# radio_board.net
KiCad netlist of a schematic drawn in EAGLE
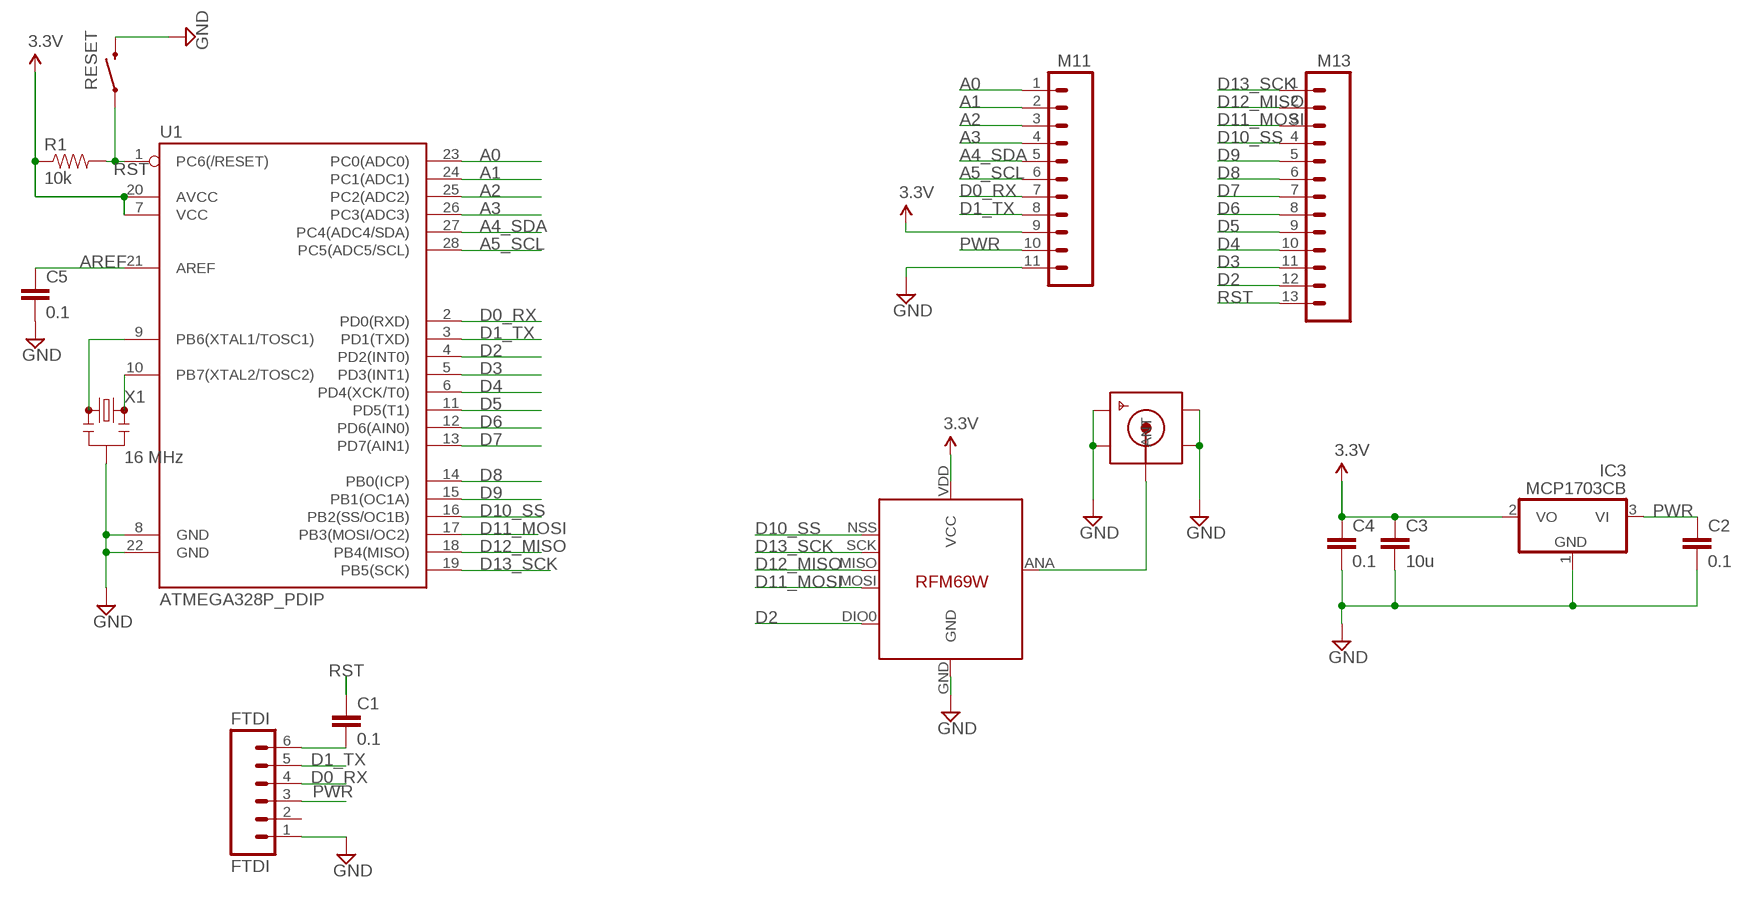
[diagram p0: schematic, sheet 1]

(export (version "E")
  (design (tool "Eeschema 10.0.6"))
  (components
    (comp (ref "C1")
      (value "0.1")
      (footprint "eagle-import:CAP-PTH-SMALL")
      (libsource (lib "eagle-import") (part "CAPPTH"))
    )
    (comp (ref "C2")
      (value "0.1")
      (footprint "eagle-import:CAP-PTH-SMALL")
      (libsource (lib "eagle-import") (part "CAPPTH"))
    )
    (comp (ref "C3")
      (value "10u")
      (footprint "eagle-import:CAP-PTH-SMALL")
      (libsource (lib "eagle-import") (part "CAPPTH"))
    )
    (comp (ref "C4")
      (value "0.1")
      (footprint "eagle-import:CAP-PTH-SMALL")
      (libsource (lib "eagle-import") (part "CAPPTH"))
    )
    (comp (ref "C5")
      (value "0.1")
      (footprint "eagle-import:CAP-PTH-SMALL")
      (libsource (lib "eagle-import") (part "CAPPTH"))
    )
    (comp (ref "DIGITALSIDE")
      (value "M13")
      (footprint "eagle-import:1X13")
      (libsource (lib "eagle-import") (part "M13"))
    )
    (comp (ref "FTDI")
      (value "FTDI")
      (footprint "eagle-import:1X06")
      (libsource (lib "eagle-import") (part "M06SIP"))
    )
    (comp (ref "IC3")
      (value "MCP1703CB")
      (footprint "eagle-import:SOT23")
      (libsource (lib "eagle-import") (part "MCP1703CB"))
    )
    (comp (ref "M11")
      (value "M11PTH")
      (footprint "eagle-import:1X11")
      (libsource (lib "eagle-import") (part "M11PTH"))
    )
    (comp (ref "R1")
      (value "10k")
      (footprint "eagle-import:AXIAL-0.4")
      (libsource (lib "eagle-import") (part "RESISTORPTH-1/4W"))
    )
    (comp (ref "RESET")
      (value "SWITCH-MOMENTARY-2SMD")
      (footprint "eagle-import:TACTILE-SWITCH-SMD")
      (libsource (lib "eagle-import") (part "SWITCH-MOMENTARY-2SMD"))
    )
    (comp (ref "SMA_CONNECTOR")
      (value "SMACONNECTOR_EDGE")
      (footprint "eagle-import:SMA_EDGELAUNCH")
      (libsource (lib "eagle-import") (part "SMACONNECTOR_EDGE"))
    )
    (comp (ref "U$5")
      (value "RFM69HW")
      (footprint "eagle-import:RFM69W-MINPADS")
      (libsource (lib "eagle-import") (part "RFM69"))
    )
    (comp (ref "U1")
      (value "ATMEGA328P_PDIP")
      (footprint "eagle-import:DIL28-3")
      (libsource (lib "eagle-import") (part "ATMEGA328P_PDIP"))
    )
    (comp (ref "X1")
      (value "16 MHz")
      (footprint "eagle-import:RESONATOR-PTH")
      (libsource (lib "eagle-import") (part "RESONATORPTH"))
    )
  )
  (nets
    (net (code "1") (name "/A0") (class "Default")
      (node (ref "M11") (pin "1") (pinfunction "1_1") (pintype "passive"))
      (node (ref "U1") (pin "23") (pinfunction "PC0(ADC0)_23") (pintype "bidirectional"))
    )
    (net (code "2") (name "/A1") (class "Default")
      (node (ref "M11") (pin "2") (pinfunction "2_2") (pintype "passive"))
      (node (ref "U1") (pin "24") (pinfunction "PC1(ADC1)_24") (pintype "bidirectional"))
    )
    (net (code "3") (name "/A2") (class "Default")
      (node (ref "M11") (pin "3") (pinfunction "3_3") (pintype "passive"))
      (node (ref "U1") (pin "25") (pinfunction "PC2(ADC2)_25") (pintype "bidirectional"))
    )
    (net (code "4") (name "/A3") (class "Default")
      (node (ref "M11") (pin "4") (pinfunction "4_4") (pintype "passive"))
      (node (ref "U1") (pin "26") (pinfunction "PC3(ADC3)_26") (pintype "bidirectional"))
    )
    (net (code "5") (name "/A4_SDA") (class "Default")
      (node (ref "M11") (pin "5") (pinfunction "5_5") (pintype "passive"))
      (node (ref "U1") (pin "27") (pinfunction "PC4(ADC4/SDA)_27") (pintype "bidirectional"))
    )
    (net (code "6") (name "/A5_SCL") (class "Default")
      (node (ref "M11") (pin "6") (pinfunction "6_6") (pintype "passive"))
      (node (ref "U1") (pin "28") (pinfunction "PC5(ADC5/SCL)_28") (pintype "bidirectional"))
    )
    (net (code "7") (name "/AREF") (class "Default")
      (node (ref "C5") (pin "1") (pinfunction "1_1") (pintype "passive"))
      (node (ref "U1") (pin "21") (pinfunction "AREF_21") (pintype "bidirectional"))
    )
    (net (code "8") (name "/D0_RX") (class "Default")
      (node (ref "FTDI") (pin "4") (pinfunction "4_4") (pintype "passive"))
      (node (ref "M11") (pin "7") (pinfunction "7_7") (pintype "passive"))
      (node (ref "U1") (pin "2") (pinfunction "PD0(RXD)_2") (pintype "bidirectional"))
    )
    (net (code "9") (name "/D1_TX") (class "Default")
      (node (ref "FTDI") (pin "5") (pinfunction "5_5") (pintype "passive"))
      (node (ref "M11") (pin "8") (pinfunction "8_8") (pintype "passive"))
      (node (ref "U1") (pin "3") (pinfunction "PD1(TXD)_3") (pintype "bidirectional"))
    )
    (net (code "10") (name "/D2") (class "Default")
      (node (ref "DIGITALSIDE") (pin "12") (pinfunction "12_12") (pintype "passive"))
      (node (ref "U$5") (pin "DIO0") (pinfunction "DIO0_DIO0") (pintype "open_collector"))
      (node (ref "U1") (pin "4") (pinfunction "PD2(INT0)_4") (pintype "bidirectional"))
    )
    (net (code "11") (name "/D3") (class "Default")
      (node (ref "DIGITALSIDE") (pin "11") (pinfunction "11_11") (pintype "passive"))
      (node (ref "U1") (pin "5") (pinfunction "PD3(INT1)_5") (pintype "bidirectional"))
    )
    (net (code "12") (name "/D4") (class "Default")
      (node (ref "DIGITALSIDE") (pin "10") (pinfunction "10_10") (pintype "passive"))
      (node (ref "U1") (pin "6") (pinfunction "PD4(XCK/T0)_6") (pintype "bidirectional"))
    )
    (net (code "13") (name "/D5") (class "Default")
      (node (ref "DIGITALSIDE") (pin "9") (pinfunction "9_9") (pintype "passive"))
      (node (ref "U1") (pin "11") (pinfunction "PD5(T1)_11") (pintype "bidirectional"))
    )
    (net (code "14") (name "/D6") (class "Default")
      (node (ref "DIGITALSIDE") (pin "8") (pinfunction "8_8") (pintype "passive"))
      (node (ref "U1") (pin "12") (pinfunction "PD6(AIN0)_12") (pintype "bidirectional"))
    )
    (net (code "15") (name "/D7") (class "Default")
      (node (ref "DIGITALSIDE") (pin "7") (pinfunction "7_7") (pintype "passive"))
      (node (ref "U1") (pin "13") (pinfunction "PD7(AIN1)_13") (pintype "bidirectional"))
    )
    (net (code "16") (name "/D8") (class "Default")
      (node (ref "DIGITALSIDE") (pin "6") (pinfunction "6_6") (pintype "passive"))
      (node (ref "U1") (pin "14") (pinfunction "PB0(ICP)_14") (pintype "bidirectional"))
    )
    (net (code "17") (name "/D9") (class "Default")
      (node (ref "DIGITALSIDE") (pin "5") (pinfunction "5_5") (pintype "passive"))
      (node (ref "U1") (pin "15") (pinfunction "PB1(OC1A)_15") (pintype "bidirectional"))
    )
    (net (code "18") (name "/D10_SS") (class "Default")
      (node (ref "DIGITALSIDE") (pin "1") (pinfunction "1_1") (pintype "passive"))
      (node (ref "U$5") (pin "NSS") (pinfunction "SEL_NSS") (pintype "input"))
      (node (ref "U1") (pin "16") (pinfunction "PB2(SS/OC1B)_16") (pintype "bidirectional"))
    )
    (net (code "19") (name "/D11_MOSI") (class "Default")
      (node (ref "DIGITALSIDE") (pin "2") (pinfunction "2_2") (pintype "passive"))
      (node (ref "U$5") (pin "MOSI") (pinfunction "MOSI_MOSI") (pintype "output"))
      (node (ref "U1") (pin "17") (pinfunction "PB3(MOSI/OC2)_17") (pintype "bidirectional"))
    )
    (net (code "20") (name "/D12_MISO") (class "Default")
      (node (ref "DIGITALSIDE") (pin "3") (pinfunction "3_3") (pintype "passive"))
      (node (ref "U$5") (pin "MISO") (pinfunction "MISO_MISO") (pintype "input"))
      (node (ref "U1") (pin "18") (pinfunction "PB4(MISO)_18") (pintype "bidirectional"))
    )
    (net (code "21") (name "/D13_SCK") (class "Default")
      (node (ref "DIGITALSIDE") (pin "4") (pinfunction "4_4") (pintype "passive"))
      (node (ref "U$5") (pin "SCK") (pinfunction "SCK_SCK") (pintype "input"))
      (node (ref "U1") (pin "19") (pinfunction "PB5(SCK)_19") (pintype "bidirectional"))
    )
    (net (code "22") (name "/PWR") (class "Default")
      (node (ref "C2") (pin "1") (pinfunction "1_1") (pintype "passive"))
      (node (ref "FTDI") (pin "3") (pinfunction "3_3") (pintype "passive"))
      (node (ref "IC3") (pin "3") (pinfunction "VI_3") (pintype "input"))
      (node (ref "M11") (pin "10") (pinfunction "10_10") (pintype "passive"))
    )
    (net (code "23") (name "/RST") (class "Default")
      (node (ref "C1") (pin "1") (pinfunction "1_1") (pintype "passive"))
      (node (ref "DIGITALSIDE") (pin "13") (pinfunction "13_13") (pintype "passive"))
      (node (ref "R1") (pin "P$2") (pinfunction "2_P$2") (pintype "passive"))
      (node (ref "RESET") (pin "1") (pinfunction "1_1") (pintype "passive"))
      (node (ref "U1") (pin "1") (pinfunction "PC6(/RESET)_1") (pintype "bidirectional"))
    )
    (net (code "24") (name "3.3V") (class "Default")
      (node (ref "C3") (pin "1") (pinfunction "1_1") (pintype "passive"))
      (node (ref "C4") (pin "1") (pinfunction "1_1") (pintype "passive"))
      (node (ref "IC3") (pin "2") (pinfunction "VO_2") (pintype "passive"))
      (node (ref "M11") (pin "9") (pinfunction "9_9") (pintype "passive"))
      (node (ref "R1") (pin "P$1") (pinfunction "1_P$1") (pintype "passive"))
      (node (ref "U$5") (pin "VDD") (pinfunction "VCC_VDD") (pintype "power_in"))
      (node (ref "U1") (pin "20") (pinfunction "AVCC_20") (pintype "bidirectional"))
      (node (ref "U1") (pin "7") (pinfunction "VCC_7") (pintype "bidirectional"))
    )
    (net (code "25") (name "GND") (class "Default")
      (node (ref "C2") (pin "2") (pinfunction "2_2") (pintype "passive"))
      (node (ref "C3") (pin "2") (pinfunction "2_2") (pintype "passive"))
      (node (ref "C4") (pin "2") (pinfunction "2_2") (pintype "passive"))
      (node (ref "C5") (pin "2") (pinfunction "2_2") (pintype "passive"))
      (node (ref "FTDI") (pin "1") (pinfunction "1_1") (pintype "passive"))
      (node (ref "IC3") (pin "1") (pinfunction "GND_1") (pintype "passive"))
      (node (ref "M11") (pin "11") (pinfunction "11_11") (pintype "passive"))
      (node (ref "RESET") (pin "3") (pinfunction "2_3") (pintype "passive"))
      (node (ref "SMA_CONNECTOR") (pin "GND@1") (pinfunction "GND4_GND@1") (pintype "power_in"))
      (node (ref "SMA_CONNECTOR") (pin "GND@2") (pinfunction "GND3_GND@2") (pintype "power_in"))
      (node (ref "SMA_CONNECTOR") (pin "GND@3") (pinfunction "GND2_GND@3") (pintype "power_in"))
      (node (ref "SMA_CONNECTOR") (pin "GND@4") (pinfunction "GND1_GND@4") (pintype "power_in"))
      (node (ref "U$5") (pin "GND") (pinfunction "GND_GND") (pintype "power_in"))
      (node (ref "U1") (pin "22") (pinfunction "GND_22") (pintype "bidirectional"))
      (node (ref "U1") (pin "8") (pinfunction "GND_8") (pintype "bidirectional"))
      (node (ref "X1") (pin "2") (pinfunction "2_2") (pintype "passive"))
    )
    (net (code "26") (name "Net-(C1-Pad2)") (class "Default")
      (node (ref "C1") (pin "2") (pinfunction "2_2") (pintype "passive"))
      (node (ref "FTDI") (pin "6") (pinfunction "6_6") (pintype "passive"))
    )
    (net (code "27") (name "Net-(SMA_CONNECTOR-ANT)") (class "Default")
      (node (ref "SMA_CONNECTOR") (pin "P") (pinfunction "ANT_P") (pintype "bidirectional"))
      (node (ref "U$5") (pin "ANA") (pinfunction "ANT_ANA") (pintype "passive"))
    )
    (net (code "28") (name "Net-(U1-PB6(XTAL1{slash}TOSC1))") (class "Default")
      (node (ref "U1") (pin "9") (pinfunction "PB6(XTAL1/TOSC1)_9") (pintype "bidirectional"))
      (node (ref "X1") (pin "1") (pinfunction "1_1") (pintype "passive"))
    )
    (net (code "29") (name "Net-(U1-PB7(XTAL2{slash}TOSC2))") (class "Default")
      (node (ref "U1") (pin "10") (pinfunction "PB7(XTAL2/TOSC2)_10") (pintype "bidirectional"))
      (node (ref "X1") (pin "3") (pinfunction "3_3") (pintype "passive"))
    )
    (net (code "30") (name "unconnected-(FTDI-Pad2)") (class "Default")
      (node (ref "FTDI") (pin "2") (pinfunction "2_2") (pintype "passive"))
    )
  )
)
